# STM32L031.net
KiCad netlist of a schematic drawn in Altium Designer
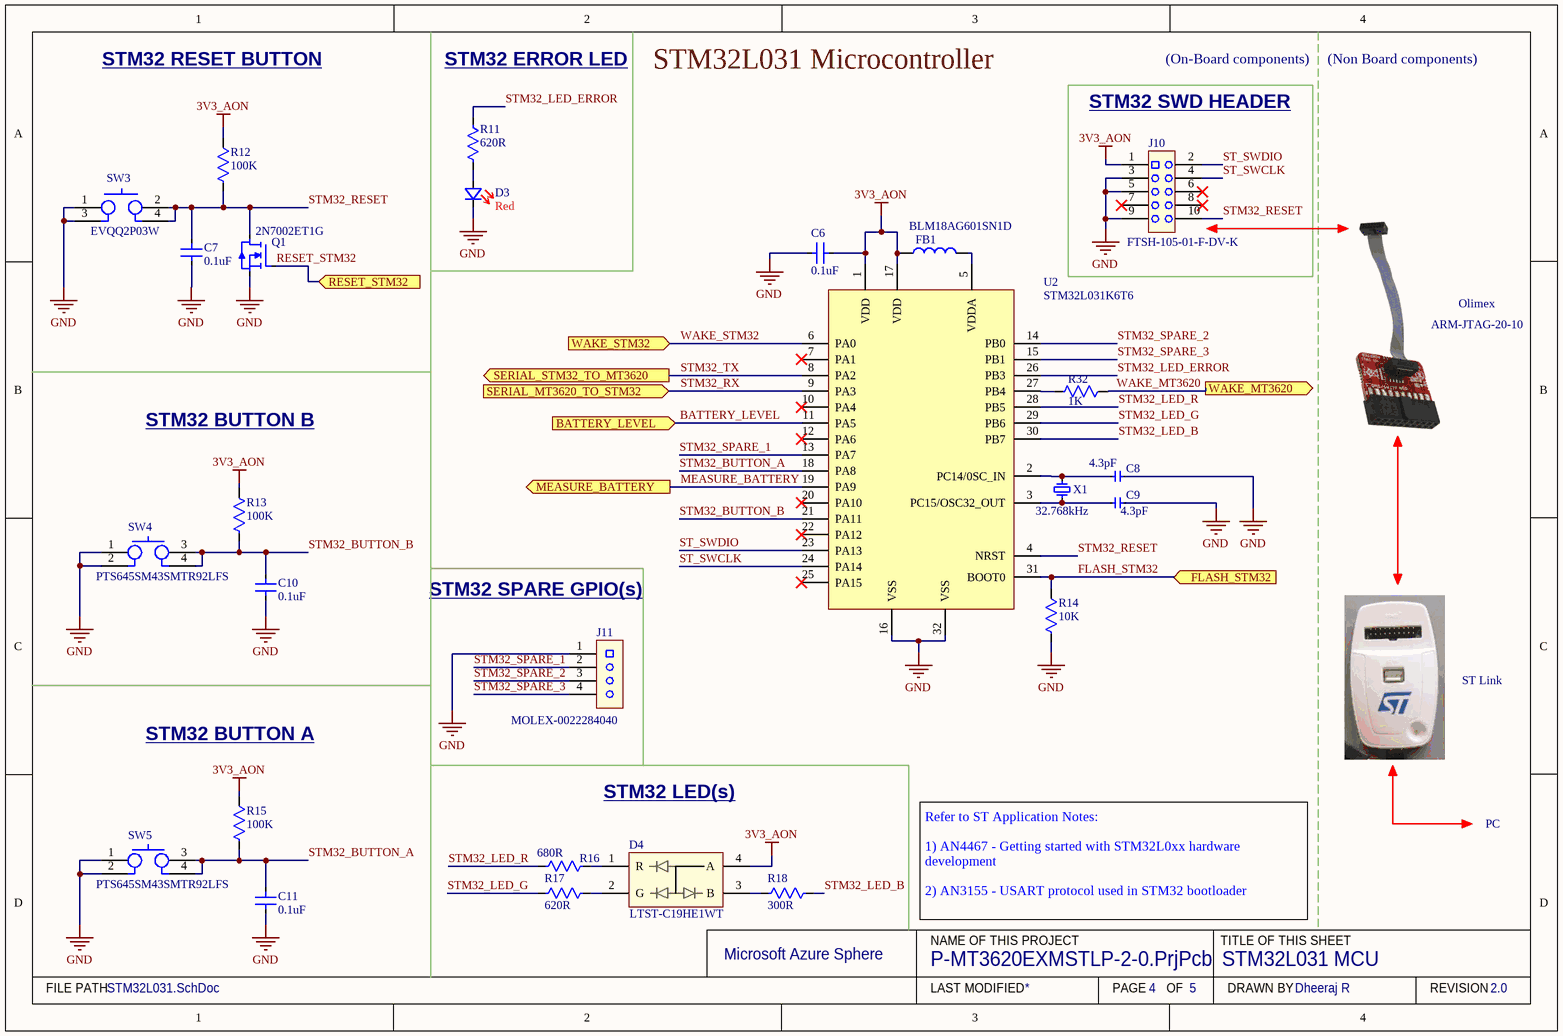
[diagram p0: STM32L031.SchDoc]

(export (version "E")
  (design (tool "Eeschema 10.0.6"))
  (components
    (comp (ref "C6")
      (value "0.1uF")
      (footprint "CC0603")
      (description "0.1uF, 0603, CC0603KRX7R8BB104, Yageo, 25V, X7R, 10%, FULL REEL")
      (fields
        (field (name "MANUFACTURER") "Yageo")
        (field (name "MANUFACTURER PART NUMBER") "CC0603KRX7R8BB104")
      )
      (libsource (lib "Yageo") (part "CC0603KRX7R8BB104"))
    )
    (comp (ref "C7")
      (value "0.1uF")
      (footprint "CC0603")
      (description "0.1uF, 0603, CC0603KRX7R8BB104, Yageo, 25V, X7R, 10%, FULL REEL")
      (fields
        (field (name "MANUFACTURER") "Yageo")
        (field (name "MANUFACTURER PART NUMBER") "CC0603KRX7R8BB104")
      )
      (libsource (lib "Yageo") (part "CC0603KRX7R8BB104"))
    )
    (comp (ref "C8")
      (value "4.3pF")
      (footprint "CAP 0603 (1608) x 1.2mm")
      (description "4.3PF 50V C0G/NP0 0603")
      (fields
        (field (name "MANUFACTURER") "Samsung")
        (field (name "MANUFACTURER PART NUMBER") "CL10C4R3CB8NNNC")
      )
      (libsource (lib "Samsung") (part "4.3pF 0603 CL10C4R3CB8NNNC"))
    )
    (comp (ref "C9")
      (value "4.3pF")
      (footprint "CAP 0603 (1608) x 1.2mm")
      (description "4.3PF 50V C0G/NP0 0603")
      (fields
        (field (name "MANUFACTURER") "Samsung")
        (field (name "MANUFACTURER PART NUMBER") "CL10C4R3CB8NNNC")
      )
      (libsource (lib "Samsung") (part "4.3pF 0603 CL10C4R3CB8NNNC"))
    )
    (comp (ref "C10")
      (value "0.1uF")
      (footprint "CC0603")
      (description "0.1uF, 0603, CC0603KRX7R8BB104, Yageo, 25V, X7R, 10%, FULL REEL")
      (fields
        (field (name "MANUFACTURER") "Yageo")
        (field (name "MANUFACTURER PART NUMBER") "CC0603KRX7R8BB104")
      )
      (libsource (lib "Yageo") (part "CC0603KRX7R8BB104"))
    )
    (comp (ref "C11")
      (value "0.1uF")
      (footprint "CC0603")
      (description "0.1uF, 0603, CC0603KRX7R8BB104, Yageo, 25V, X7R, 10%, FULL REEL")
      (fields
        (field (name "MANUFACTURER") "Yageo")
        (field (name "MANUFACTURER PART NUMBER") "CC0603KRX7R8BB104")
      )
      (libsource (lib "Yageo") (part "CC0603KRX7R8BB104"))
    )
    (comp (ref "D3")
      (value "SML-D12U")
      (footprint "Rohm SML-D12 Red")
      (description "1.6 x 0.8 x 0.55mm (0603) LED 620nm Red")
      (fields
        (field (name "MANUFACTURER") "Rohm Semiconductor")
        (field (name "MANUFACTURER PART NUMBER") "SML-D12U8WT86")
        (field (name "COLOUR") "Red")
      )
      (libsource (lib "Rohm") (part "SML-D12U"))
    )
    (comp (ref "D4")
      (value "LTST-C19HE1WT")
      (footprint "LTST-C19HE1WT")
      (description "LED RGB DIFFUSED 0606 SMD")
      (fields (field (name "MANUFACTURER") "Lite-On Inc."))
      (libsource (lib "Lite-On") (part "LTST-C19HE1WT"))
    )
    (comp (ref "FB1")
      (value "BLM18AG601SN1D")
      (footprint "BLM18P")
      (fields (field (name "MANUFACTURER") "Murata") (field (name "TOLERANCE") "25%"))
      (libsource (lib "Murata") (part "BLM18AG601SN1D"))
    )
    (comp (ref "J10")
      (value "FTSH-105-01-F-DV-K")
      (footprint "SAMTEC-FTSH-105-01-X-DV-K")
      (description "CONN HEADER 10POS DUAL .05\" SMD")
      (fields (field (name "MANUFACTURER") "Samtec Inc."))
      (libsource (lib "Samtec") (part "FTSH-105-01-F-DV-K"))
    )
    (comp (ref "J11")
      (value "MOLEX-0022284040")
      (footprint "0022284040")
      (description "CONN HEADER 4POS .100 VERT TIN")
      (fields
        (field (name "MANUFACTURER") "Molex, LLC")
        (field (name "MANUFACTURER PART NUMBER") "0022284040")
      )
      (libsource (lib "Molex") (part "MOLEX-0022284040"))
    )
    (comp (ref "Q1")
      (value "2N7002ET1G")
      (footprint "SOT23-ONS")
      (description "N-CH 60V 0.26A 3-Pin SOT-23 T/R")
      (fields (field (name "MANUFACTURER") "ON Semiconductor"))
      (libsource (lib "OnSemiconductor") (part "2N7002ET1G"))
    )
    (comp (ref "R11")
      (value "620R")
      (footprint "RC0603")
      (description "620 Ohm, 0603, 1% 0.1W(1/10W) 100ppm/ C Molded SMD Paper T/R")
      (fields
        (field (name "MANUFACTURER") "Yageo")
        (field (name "MANUFACTURER PART NUMBER") "RC0603FR-07620RL")
      )
      (libsource (lib "Yageo") (part "RC0603FR-07620RL"))
    )
    (comp (ref "R12")
      (value "100K")
      (footprint "VISHAY-0603")
      (description "100K Ohm 0603 1% 0.1W(1/10W) 100ppm Paper T/R")
      (fields
        (field (name "MANUFACTURER") "Yageo")
        (field (name "MANUFACTURER PART NUMBER") "RC0603FR-07100KL")
      )
      (libsource (lib "Yageo") (part "RC0603FR-07100KL"))
    )
    (comp (ref "R13")
      (value "100K")
      (footprint "VISHAY-0603")
      (description "100K Ohm 0603 1% 0.1W(1/10W) 100ppm Paper T/R")
      (fields
        (field (name "MANUFACTURER") "Yageo")
        (field (name "MANUFACTURER PART NUMBER") "RC0603FR-07100KL")
      )
      (libsource (lib "Yageo") (part "RC0603FR-07100KL"))
    )
    (comp (ref "R14")
      (value "10K")
      (footprint "VISHAY-0603")
      (description "10K Ohm 0603 1% 1/10W ±100ppm/°C Molded SMD Paper T/R")
      (fields
        (field (name "MANUFACTURER") "Yageo")
        (field (name "MANUFACTURER PART NUMBER") "RC0603FR-0710KL")
      )
      (libsource (lib "Yageo") (part "RC0603FR-0710KL"))
    )
    (comp (ref "R15")
      (value "100K")
      (footprint "VISHAY-0603")
      (description "100K Ohm 0603 1% 0.1W(1/10W) 100ppm Paper T/R")
      (fields
        (field (name "MANUFACTURER") "Yageo")
        (field (name "MANUFACTURER PART NUMBER") "RC0603FR-07100KL")
      )
      (libsource (lib "") (part "RC0603FR-07100KL_1"))
    )
    (comp (ref "R16")
      (value "680R")
      (footprint "RC0603")
      (description "680R, 0603 YAGEO - RC0603FR-07680RL - SMD Chip Resistor, RC Series, 50 V, Thick Film, 100 mW")
      (fields
        (field (name "MANUFACTURER") "Yageo")
        (field (name "MANUFACTURER PART NUMBER") "RC0603FR-07680RL")
      )
      (libsource (lib "Yageo") (part "RC0603FR-07680RL"))
    )
    (comp (ref "R17")
      (value "620R")
      (footprint "RC0603")
      (description "620 Ohm, 0603, 1% 0.1W(1/10W) 100ppm/ C Molded SMD Paper T/R")
      (fields
        (field (name "MANUFACTURER") "Yageo")
        (field (name "MANUFACTURER PART NUMBER") "RC0603FR-07620RL")
      )
      (libsource (lib "Yageo") (part "RC0603FR-07620RL"))
    )
    (comp (ref "R18")
      (value "300R")
      (footprint "RC0603")
      (description "300 Ohm, 0603, 1% 0.1W(1/10W) 100ppm/ C Molded SMD Paper T/R")
      (fields
        (field (name "MANUFACTURER") "Yageo")
        (field (name "MANUFACTURER PART NUMBER") "RC0603FR-07300RL")
      )
      (libsource (lib "Yageo") (part "RC0603FR-07300RL"))
    )
    (comp (ref "R32")
      (value "1K")
      (footprint "YAGEO-0603:RC0603")
      (description "1K 5% 1/10W 0603")
      (fields
        (field (name "MANUFACTURER") "Yageo")
        (field (name "MANUFACTURER PART NUMBER") "RC0603JR-071KL")
      )
      (libsource (lib "Yageo") (part "RC0603JR-071KL"))
    )
    (comp (ref "SW3")
      (value "SWI TACT SPN0 PANASONIC EVQQ2P03W")
      (footprint "EVQQ2P03W")
      (description "PANASONIC - EVQQ2P03W - SWITCH, SPNO, SMD")
      (fields (field (name "MANUFACTURER") "PANASONIC") (field (name "MANUFACTURER PART NUMBER") "EVQQ2P03W"))
      (libsource (lib "switch") (part "SWI TACT SPN0 PANASONIC EVQQ2P03W"))
    )
    (comp (ref "SW4")
      (value "PTS645SM43SMTR92LFS")
      (footprint "C&K PTS645SM43SMTR92LFS")
      (description "SWITCH TACTILE SPST-NO 0.05A 12V")
      (fields (field (name "MANUFACTURER") "ITT C&K"))
      (libsource (lib "C&K") (part "PTS645SM43SMTR92LFS"))
    )
    (comp (ref "SW5")
      (value "PTS645SM43SMTR92LFS")
      (footprint "C&K PTS645SM43SMTR92LFS")
      (description "SWITCH TACTILE SPST-NO 0.05A 12V")
      (fields (field (name "MANUFACTURER") "ITT C&K"))
      (libsource (lib "C&K") (part "PTS645SM43SMTR92LFS"))
    )
    (comp (ref "U2")
      (value "STM32L031K6T6")
      (footprint "LQFP32-ST")
      (description "IC MCU 32BIT 32KB FLASH 32LQFP")
      (fields (field (name "MANUFACTURER") "STMicroelectronics"))
      (libsource (lib "ST") (part "STM32L031K6T6"))
    )
    (comp (ref "X1")
      (value "32.768kHz")
      (footprint "XTAL_NX3215SA-00")
      (description "CRYSTAL 32.768KHZ 6PF SMD")
      (fields
        (field (name "MANUFACTURER") "NDK")
        (field (name "MANUFACTURER PART NUMBER") "NX3215SA-32.768KHZ-EXS00A-MU00525")
      )
      (libsource (lib "NDKAmerica") (part "NX3215SA-32.768KHZ-EXS00A-MU00525"))
    )
  )
  (nets
    (net (code "1") (name "/BATTERY_LEVEL") (class "Default")
      (node (ref "U2") (pin "11") (pinfunction "PA5_11") (pintype "passive"))
    )
    (net (code "2") (name "/FLASH_STM32") (class "Default")
      (node (ref "R14") (pin "2") (pinfunction "2_2") (pintype "passive"))
      (node (ref "U2") (pin "31") (pinfunction "BOOT0_31") (pintype "passive"))
    )
    (net (code "3") (name "/MEASURE_BATTERY") (class "Default")
      (node (ref "U2") (pin "19") (pinfunction "PA9_19") (pintype "passive"))
    )
    (net (code "4") (name "/RESET_STM32") (class "Default")
      (node (ref "Q1") (pin "1") (pinfunction "1_1") (pintype "passive"))
    )
    (net (code "5") (name "/STM32_BUTTON_A") (class "Default")
      (node (ref "C11") (pin "2") (pinfunction "2_2") (pintype "passive"))
      (node (ref "R15") (pin "1") (pinfunction "1_1") (pintype "passive"))
      (node (ref "SW5") (pin "3") (pinfunction "3_3") (pintype "passive"))
      (node (ref "SW5") (pin "4") (pinfunction "4_4") (pintype "passive"))
      (node (ref "U2") (pin "18") (pinfunction "PA8_18") (pintype "passive"))
    )
    (net (code "6") (name "/STM32_BUTTON_B") (class "Default")
      (node (ref "C10") (pin "2") (pinfunction "2_2") (pintype "passive"))
      (node (ref "R13") (pin "1") (pinfunction "1_1") (pintype "passive"))
      (node (ref "SW4") (pin "3") (pinfunction "3_3") (pintype "passive"))
      (node (ref "SW4") (pin "4") (pinfunction "4_4") (pintype "passive"))
      (node (ref "U2") (pin "21") (pinfunction "PA11_21") (pintype "passive"))
    )
    (net (code "7") (name "/STM32_LED_B") (class "Default")
      (node (ref "R18") (pin "2") (pinfunction "2_2") (pintype "passive"))
      (node (ref "U2") (pin "30") (pinfunction "PB7_30") (pintype "passive"))
    )
    (net (code "8") (name "/STM32_LED_ERROR") (class "Default")
      (node (ref "R11") (pin "2") (pinfunction "2_2") (pintype "passive"))
      (node (ref "U2") (pin "26") (pinfunction "PB3_26") (pintype "passive"))
    )
    (net (code "9") (name "/STM32_LED_G") (class "Default")
      (node (ref "R17") (pin "1") (pinfunction "1_1") (pintype "passive"))
      (node (ref "U2") (pin "29") (pinfunction "PB6_29") (pintype "passive"))
    )
    (net (code "10") (name "/STM32_LED_R") (class "Default")
      (node (ref "R16") (pin "1") (pinfunction "1_1") (pintype "passive"))
      (node (ref "U2") (pin "28") (pinfunction "PB5_28") (pintype "passive"))
    )
    (net (code "11") (name "/STM32_RESET") (class "Default")
      (node (ref "C7") (pin "2") (pinfunction "2_2") (pintype "passive"))
      (node (ref "J10") (pin "10") (pinfunction "10_10") (pintype "passive"))
      (node (ref "Q1") (pin "3") (pinfunction "3_3") (pintype "passive"))
      (node (ref "R12") (pin "1") (pinfunction "1_1") (pintype "passive"))
      (node (ref "SW3") (pin "2") (pinfunction "2_2") (pintype "passive"))
      (node (ref "SW3") (pin "4") (pinfunction "4_4") (pintype "passive"))
      (node (ref "U2") (pin "4") (pinfunction "NRST_4") (pintype "passive"))
    )
    (net (code "12") (name "/STM32_RX") (class "Default")
      (node (ref "U2") (pin "9") (pinfunction "PA3_9") (pintype "passive"))
    )
    (net (code "13") (name "/STM32_SPARE_1") (class "Default")
      (node (ref "J11") (pin "2") (pinfunction "2_2") (pintype "passive"))
      (node (ref "U2") (pin "13") (pinfunction "PA7_13") (pintype "passive"))
    )
    (net (code "14") (name "/STM32_SPARE_2") (class "Default")
      (node (ref "J11") (pin "3") (pinfunction "3_3") (pintype "passive"))
      (node (ref "U2") (pin "14") (pinfunction "PB0_14") (pintype "passive"))
    )
    (net (code "15") (name "/STM32_SPARE_3") (class "Default")
      (node (ref "J11") (pin "4") (pinfunction "4_4") (pintype "passive"))
      (node (ref "U2") (pin "15") (pinfunction "PB1_15") (pintype "passive"))
    )
    (net (code "16") (name "/STM32_TX") (class "Default")
      (node (ref "U2") (pin "8") (pinfunction "PA2_8") (pintype "passive"))
    )
    (net (code "17") (name "/ST_SWCLK") (class "Default")
      (node (ref "J10") (pin "4") (pinfunction "4_4") (pintype "passive"))
      (node (ref "U2") (pin "24") (pinfunction "PA14_24") (pintype "passive"))
    )
    (net (code "18") (name "/ST_SWDIO") (class "Default")
      (node (ref "J10") (pin "2") (pinfunction "2_2") (pintype "passive"))
      (node (ref "U2") (pin "23") (pinfunction "PA13_23") (pintype "passive"))
    )
    (net (code "19") (name "/WAKE_MT3620") (class "Default")
      (node (ref "R32") (pin "2") (pinfunction "2_2") (pintype "passive"))
    )
    (net (code "20") (name "/WAKE_STM32") (class "Default")
      (node (ref "U2") (pin "6") (pinfunction "PA0_6") (pintype "passive"))
    )
    (net (code "21") (name "3V3_AON") (class "Default")
      (node (ref "C6") (pin "2") (pinfunction "2_2") (pintype "passive"))
      (node (ref "D4") (pin "4") (pinfunction "A_4") (pintype "passive"))
      (node (ref "FB1") (pin "1") (pinfunction "1_1") (pintype "passive"))
      (node (ref "J10") (pin "1") (pinfunction "1_1") (pintype "passive"))
      (node (ref "R12") (pin "2") (pinfunction "2_2") (pintype "passive"))
      (node (ref "R13") (pin "2") (pinfunction "2_2") (pintype "passive"))
      (node (ref "R15") (pin "2") (pinfunction "2_2") (pintype "passive"))
      (node (ref "U2") (pin "1") (pinfunction "VDD_1") (pintype "passive"))
      (node (ref "U2") (pin "17") (pinfunction "VDD_17") (pintype "passive"))
    )
    (net (code "22") (name "GND") (class "Default")
      (node (ref "C10") (pin "1") (pinfunction "1_1") (pintype "passive"))
      (node (ref "C11") (pin "1") (pinfunction "1_1") (pintype "passive"))
      (node (ref "C6") (pin "1") (pinfunction "1_1") (pintype "passive"))
      (node (ref "C7") (pin "1") (pinfunction "1_1") (pintype "passive"))
      (node (ref "C8") (pin "1") (pinfunction "1_1") (pintype "passive"))
      (node (ref "C9") (pin "1") (pinfunction "1_1") (pintype "passive"))
      (node (ref "D3") (pin "1") (pinfunction "K_1") (pintype "passive"))
      (node (ref "J10") (pin "3") (pinfunction "3_3") (pintype "passive"))
      (node (ref "J10") (pin "5") (pinfunction "5_5") (pintype "passive"))
      (node (ref "J10") (pin "9") (pinfunction "9_9") (pintype "passive"))
      (node (ref "J11") (pin "1") (pinfunction "1_1") (pintype "passive"))
      (node (ref "Q1") (pin "2") (pinfunction "2_2") (pintype "passive"))
      (node (ref "R14") (pin "1") (pinfunction "1_1") (pintype "passive"))
      (node (ref "SW3") (pin "1") (pinfunction "1_1") (pintype "passive"))
      (node (ref "SW3") (pin "3") (pinfunction "3_3") (pintype "passive"))
      (node (ref "SW4") (pin "1") (pinfunction "1_1") (pintype "passive"))
      (node (ref "SW4") (pin "2") (pinfunction "2_2") (pintype "passive"))
      (node (ref "SW5") (pin "1") (pinfunction "1_1") (pintype "passive"))
      (node (ref "SW5") (pin "2") (pinfunction "2_2") (pintype "passive"))
      (node (ref "U2") (pin "16") (pinfunction "VSS_16") (pintype "passive"))
      (node (ref "U2") (pin "32") (pinfunction "VSS_32") (pintype "passive"))
    )
    (net (code "23") (name "Net-(D3-A)") (class "Default")
      (node (ref "D3") (pin "2") (pinfunction "A_2") (pintype "passive"))
      (node (ref "R11") (pin "1") (pinfunction "1_1") (pintype "passive"))
    )
    (net (code "24") (name "Net-(D4-B)") (class "Default")
      (node (ref "D4") (pin "3") (pinfunction "B_3") (pintype "passive"))
      (node (ref "R18") (pin "1") (pinfunction "1_1") (pintype "passive"))
    )
    (net (code "25") (name "Net-(D4-G)") (class "Default")
      (node (ref "D4") (pin "2") (pinfunction "G_2") (pintype "passive"))
      (node (ref "R17") (pin "2") (pinfunction "2_2") (pintype "passive"))
    )
    (net (code "26") (name "Net-(D4-R)") (class "Default")
      (node (ref "D4") (pin "1") (pinfunction "R_1") (pintype "passive"))
      (node (ref "R16") (pin "2") (pinfunction "2_2") (pintype "passive"))
    )
    (net (code "27") (name "Net-(U2-PB4)") (class "Default")
      (node (ref "R32") (pin "1") (pinfunction "1_1") (pintype "passive"))
      (node (ref "U2") (pin "27") (pinfunction "PB4_27") (pintype "passive"))
    )
    (net (code "28") (name "Net-(U2-PC14{slash}0SC_IN)") (class "Default")
      (node (ref "C8") (pin "2") (pinfunction "2_2") (pintype "passive"))
      (node (ref "U2") (pin "2") (pinfunction "PC14/0SC_IN_2") (pintype "passive"))
      (node (ref "X1") (pin "1") (pinfunction "1_1") (pintype "passive"))
    )
    (net (code "29") (name "Net-(U2-PC15{slash}OSC32_OUT)") (class "Default")
      (node (ref "C9") (pin "2") (pinfunction "2_2") (pintype "passive"))
      (node (ref "U2") (pin "3") (pinfunction "PC15/OSC32_OUT_3") (pintype "passive"))
      (node (ref "X1") (pin "2") (pinfunction "2_2") (pintype "passive"))
    )
    (net (code "30") (name "Net-(U2-VDDA)") (class "Default")
      (node (ref "FB1") (pin "2") (pinfunction "2_2") (pintype "passive"))
      (node (ref "U2") (pin "5") (pinfunction "VDDA_5") (pintype "passive"))
    )
    (net (code "31") (name "unconnected-(J10-Pad6)") (class "Default")
      (node (ref "J10") (pin "6") (pinfunction "6_6") (pintype "passive+no_connect"))
    )
    (net (code "32") (name "unconnected-(J10-Pad7)") (class "Default")
      (node (ref "J10") (pin "7") (pinfunction "7_7") (pintype "passive+no_connect"))
    )
    (net (code "33") (name "unconnected-(J10-Pad8)") (class "Default")
      (node (ref "J10") (pin "8") (pinfunction "8_8") (pintype "passive+no_connect"))
    )
    (net (code "34") (name "unconnected-(U2-PA1-Pad7)") (class "Default")
      (node (ref "U2") (pin "7") (pinfunction "PA1_7") (pintype "passive+no_connect"))
    )
    (net (code "35") (name "unconnected-(U2-PA4-Pad10)") (class "Default")
      (node (ref "U2") (pin "10") (pinfunction "PA4_10") (pintype "passive+no_connect"))
    )
    (net (code "36") (name "unconnected-(U2-PA6-Pad12)") (class "Default")
      (node (ref "U2") (pin "12") (pinfunction "PA6_12") (pintype "passive+no_connect"))
    )
    (net (code "37") (name "unconnected-(U2-PA10-Pad20)") (class "Default")
      (node (ref "U2") (pin "20") (pinfunction "PA10_20") (pintype "passive+no_connect"))
    )
    (net (code "38") (name "unconnected-(U2-PA12-Pad22)") (class "Default")
      (node (ref "U2") (pin "22") (pinfunction "PA12_22") (pintype "passive+no_connect"))
    )
    (net (code "39") (name "unconnected-(U2-PA15-Pad25)") (class "Default")
      (node (ref "U2") (pin "25") (pinfunction "PA15_25") (pintype "passive+no_connect"))
    )
  )
)
